# sch.net
KiCad netlist of a schematic drawn in Altium Designer
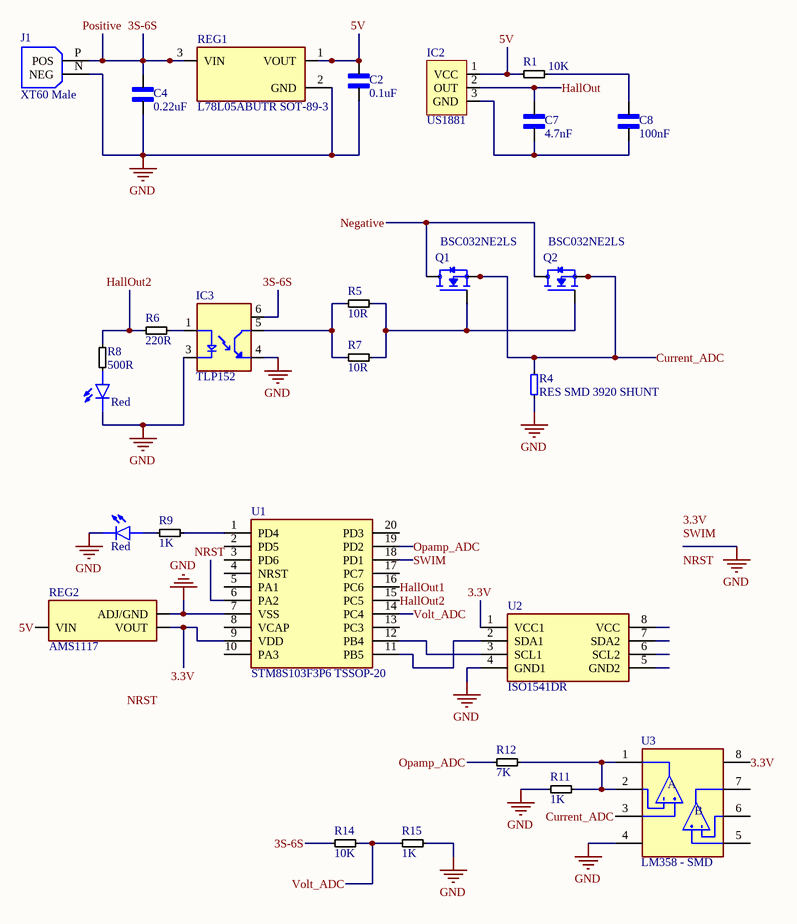
[diagram p0: sch.SchDoc]

(export (version "E")
  (design (tool "Eeschema 10.0.6"))
  (components
    (comp (ref "C2")
      (value "0.1uF")
      (footprint "0805 SMD CAP")
      (libsource (lib "MYS-Library") (part "CAP SMD 0805"))
    )
    (comp (ref "C4")
      (value "0.22uF")
      (footprint "0805 SMD CAP")
      (libsource (lib "MYS-Library") (part "CAP SMD 0805"))
    )
    (comp (ref "C7")
      (value "4.7nF")
      (footprint "0805 SMD CAP")
      (libsource (lib "MYS-Library") (part "CAP SMD 0805"))
    )
    (comp (ref "C8")
      (value "100nF")
      (footprint "0805 SMD CAP")
      (libsource (lib "MYS-Library") (part "CAP SMD 0805"))
    )
    (comp (ref "D2")
      (value "Red")
      (footprint "0805 SMD LED")
      (libsource (lib "MYS-Library") (part "LED 0805 SMD"))
    )
    (comp (ref "D3")
      (value "Red")
      (footprint "0805 SMD LED")
      (libsource (lib "MYS-Library") (part "LED 0805 SMD"))
    )
    (comp (ref "IC2") (value "US1881") (footprint "UA") (libsource (lib "MYS-Library") (part "US1881")))
    (comp (ref "IC3")
      (value "TLP152")
      (footprint "SOIC-6")
      (libsource (lib "MYS-Library") (part "TLP152-SMD"))
    )
    (comp (ref "J1")
      (value "XT60 Male")
      (footprint "XT60 Male Pin")
      (libsource (lib "MYS-Library") (part "XT60 Male Pin"))
    )
    (comp (ref "Q1")
      (value "BSC032NE2LS")
      (footprint "TDSON-8")
      (libsource (lib "MYS-Library") (part "TDSON-8 MOSFET"))
    )
    (comp (ref "Q2")
      (value "BSC032NE2LS")
      (footprint "TDSON-8")
      (libsource (lib "MYS-Library") (part "TDSON-8 MOSFET"))
    )
    (comp (ref "R1")
      (value "10K")
      (footprint "0805 SMD RES")
      (libsource (lib "MYS-Library") (part "RES SMD 0805"))
    )
    (comp (ref "R4")
      (value "RES SMD 3920 SHUNT")
      (footprint "RES 3920 SMD")
      (libsource (lib "MYS-Library") (part "RES SMD 3920 SHUNT"))
    )
    (comp (ref "R5")
      (value "10R")
      (footprint "0805 SMD RES")
      (libsource (lib "MYS-Library") (part "RES SMD 0805"))
    )
    (comp (ref "R6")
      (value "220R")
      (footprint "0805 SMD RES")
      (libsource (lib "MYS-Library") (part "RES SMD 0805"))
    )
    (comp (ref "R7")
      (value "10R")
      (footprint "0805 SMD RES")
      (libsource (lib "MYS-Library") (part "RES SMD 0805"))
    )
    (comp (ref "R8")
      (value "500R")
      (footprint "0805 SMD RES")
      (libsource (lib "MYS-Library") (part "RES SMD 0805"))
    )
    (comp (ref "R9")
      (value "1K")
      (footprint "0805 SMD RES")
      (libsource (lib "MYS-Library") (part "RES SMD 0805"))
    )
    (comp (ref "R11")
      (value "1K")
      (footprint "0805 SMD RES")
      (libsource (lib "MYS-Library") (part "RES SMD 0805"))
    )
    (comp (ref "R12")
      (value "7K")
      (footprint "0805 SMD RES")
      (libsource (lib "MYS-Library") (part "RES SMD 0805"))
    )
    (comp (ref "R14")
      (value "10K")
      (footprint "0805 SMD RES")
      (libsource (lib "MYS-Library") (part "RES SMD 0805"))
    )
    (comp (ref "R15")
      (value "1K")
      (footprint "0805 SMD RES")
      (libsource (lib "MYS-Library") (part "RES SMD 0805"))
    )
    (comp (ref "REG1")
      (value "L78L05ABUTR SOT-89-3")
      (footprint "SOT89-3")
      (libsource (lib "MYS-Library") (part "L78L05ABUTR"))
    )
    (comp (ref "REG2")
      (value "AMS1117")
      (footprint "SOT-223")
      (libsource (lib "MYS-Library") (part "AMS1117"))
    )
    (comp (ref "U1")
      (value "STM8S103F3P6 TSSOP-20")
      (footprint "TSSOP-20")
      (libsource (lib "MYS-Library") (part "STM8S103F3P6"))
    )
    (comp (ref "U2")
      (value "ISO1541DR")
      (footprint "SOIC-8")
      (libsource (lib "MYS-Library") (part "ISO1541DR"))
    )
    (comp (ref "U3")
      (value "LM358 - SMD")
      (footprint "SOIC-8")
      (libsource (lib "MYS-Library") (part "LM358 - SMD"))
    )
  )
  (nets
    (net (code "1") (name "/3.3V") (class "Default")
      (node (ref "REG2") (pin "2") (pinfunction "VOUT_2") (pintype "passive"))
      (node (ref "U1") (pin "9") (pinfunction "VDD_9") (pintype "passive"))
      (node (ref "U2") (pin "1") (pinfunction "VCC1_1") (pintype "passive"))
      (node (ref "U3") (pin "8") (pinfunction "V+_8") (pintype "passive"))
    )
    (net (code "2") (name "/3S-6S") (class "Default")
      (node (ref "C4") (pin "1") (pinfunction "1_1") (pintype "passive"))
      (node (ref "IC3") (pin "6") (pinfunction "Vcc_6") (pintype "passive"))
      (node (ref "J1") (pin "P") (pinfunction "POS_P") (pintype "passive"))
      (node (ref "R14") (pin "1") (pinfunction "1_1") (pintype "passive"))
      (node (ref "REG1") (pin "3") (pinfunction "VIN_3") (pintype "passive"))
    )
    (net (code "3") (name "/5V") (class "Default")
      (node (ref "C2") (pin "1") (pinfunction "1_1") (pintype "passive"))
      (node (ref "IC2") (pin "1") (pinfunction "VCC_1") (pintype "passive"))
      (node (ref "R1") (pin "1") (pinfunction "1_1") (pintype "passive"))
      (node (ref "REG1") (pin "1") (pinfunction "VOUT_1") (pintype "passive"))
      (node (ref "REG2") (pin "3") (pinfunction "VIN_3") (pintype "passive"))
    )
    (net (code "4") (name "/Current_ADC") (class "Default")
      (node (ref "Q1") (pin "1") (pinfunction "S_1") (pintype "passive"))
      (node (ref "Q1") (pin "2") (pinfunction "S_2") (pintype "passive"))
      (node (ref "Q1") (pin "3") (pinfunction "S_3") (pintype "passive"))
      (node (ref "Q2") (pin "1") (pinfunction "S_1") (pintype "passive"))
      (node (ref "Q2") (pin "2") (pinfunction "S_2") (pintype "passive"))
      (node (ref "Q2") (pin "3") (pinfunction "S_3") (pintype "passive"))
      (node (ref "R4") (pin "2") (pinfunction "2_2") (pintype "passive"))
      (node (ref "U3") (pin "3") (pinfunction "IN1+_3") (pintype "passive"))
    )
    (net (code "5") (name "/HallOut") (class "Default")
      (node (ref "C7") (pin "1") (pinfunction "1_1") (pintype "passive"))
      (node (ref "IC2") (pin "2") (pinfunction "OUT_2") (pintype "passive"))
    )
    (net (code "6") (name "/HallOut1") (class "Default")
      (node (ref "U1") (pin "16") (pinfunction "PC6_16") (pintype "passive"))
    )
    (net (code "7") (name "/HallOut2") (class "Default")
      (node (ref "R6") (pin "1") (pinfunction "1_1") (pintype "passive"))
      (node (ref "R8") (pin "2") (pinfunction "2_2") (pintype "passive"))
      (node (ref "U1") (pin "15") (pinfunction "PC5_15") (pintype "passive"))
    )
    (net (code "8") (name "/NRST") (class "Default")
      (node (ref "U1") (pin "6") (pinfunction "PA2_6") (pintype "passive"))
    )
    (net (code "9") (name "/Negative") (class "Default")
      (node (ref "Q1") (pin "5") (pinfunction "D_5") (pintype "passive"))
      (node (ref "Q2") (pin "5") (pinfunction "D_5") (pintype "passive"))
    )
    (net (code "10") (name "/Opamp_ADC") (class "Default")
      (node (ref "R12") (pin "1") (pinfunction "1_1") (pintype "passive"))
      (node (ref "U1") (pin "19") (pinfunction "PD2_19") (pintype "passive"))
    )
    (net (code "11") (name "/SWIM") (class "Default")
      (node (ref "U1") (pin "18") (pinfunction "PD1_18") (pintype "passive"))
    )
    (net (code "12") (name "/Volt_ADC") (class "Default")
      (node (ref "R14") (pin "2") (pinfunction "2_2") (pintype "passive"))
      (node (ref "R15") (pin "1") (pinfunction "1_1") (pintype "passive"))
      (node (ref "U1") (pin "14") (pinfunction "PC4_14") (pintype "passive"))
    )
    (net (code "13") (name "GND") (class "Default")
      (node (ref "C2") (pin "2") (pinfunction "2_2") (pintype "passive"))
      (node (ref "C4") (pin "2") (pinfunction "2_2") (pintype "passive"))
      (node (ref "D2") (pin "C") (pinfunction "C_C") (pintype "passive"))
      (node (ref "D3") (pin "C") (pinfunction "C_C") (pintype "passive"))
      (node (ref "IC3") (pin "3") (pinfunction "C_3") (pintype "passive"))
      (node (ref "IC3") (pin "4") (pinfunction "GND_4") (pintype "passive"))
      (node (ref "J1") (pin "N") (pinfunction "NEG_N") (pintype "passive"))
      (node (ref "R11") (pin "1") (pinfunction "1_1") (pintype "passive"))
      (node (ref "R15") (pin "2") (pinfunction "2_2") (pintype "passive"))
      (node (ref "R4") (pin "1") (pinfunction "1_1") (pintype "passive"))
      (node (ref "REG1") (pin "2") (pinfunction "GND_2") (pintype "passive"))
      (node (ref "REG2") (pin "1") (pinfunction "ADJ/GND_1") (pintype "power_in"))
      (node (ref "U1") (pin "7") (pinfunction "VSS_7") (pintype "passive"))
      (node (ref "U2") (pin "4") (pinfunction "GND1_4") (pintype "passive"))
      (node (ref "U3") (pin "4") (pinfunction "V-_4") (pintype "passive"))
    )
    (net (code "14") (name "Net-(C8-Pad1)") (class "Default")
      (node (ref "C8") (pin "1") (pinfunction "1_1") (pintype "passive"))
      (node (ref "R1") (pin "2") (pinfunction "2_2") (pintype "passive"))
    )
    (net (code "15") (name "Net-(D2-PadA)") (class "Default")
      (node (ref "D2") (pin "A") (pinfunction "A_A") (pintype "passive"))
      (node (ref "R8") (pin "1") (pinfunction "1_1") (pintype "passive"))
    )
    (net (code "16") (name "Net-(D3-PadA)") (class "Default")
      (node (ref "D3") (pin "A") (pinfunction "A_A") (pintype "passive"))
      (node (ref "R9") (pin "2") (pinfunction "2_2") (pintype "passive"))
    )
    (net (code "17") (name "Net-(IC2-GND)") (class "Default")
      (node (ref "C7") (pin "2") (pinfunction "2_2") (pintype "passive"))
      (node (ref "C8") (pin "2") (pinfunction "2_2") (pintype "passive"))
      (node (ref "IC2") (pin "3") (pinfunction "GND_3") (pintype "passive"))
    )
    (net (code "18") (name "Net-(IC3-A)") (class "Default")
      (node (ref "IC3") (pin "1") (pinfunction "A_1") (pintype "passive"))
      (node (ref "R6") (pin "2") (pinfunction "2_2") (pintype "passive"))
    )
    (net (code "19") (name "Net-(IC3-Vo)") (class "Default")
      (node (ref "IC3") (pin "5") (pinfunction "Vo_5") (pintype "passive"))
      (node (ref "R5") (pin "1") (pinfunction "1_1") (pintype "passive"))
      (node (ref "R7") (pin "1") (pinfunction "1_1") (pintype "passive"))
    )
    (net (code "20") (name "Net-(Q1-G)") (class "Default")
      (node (ref "Q1") (pin "4") (pinfunction "G_4") (pintype "passive"))
      (node (ref "Q2") (pin "4") (pinfunction "G_4") (pintype "passive"))
      (node (ref "R5") (pin "2") (pinfunction "2_2") (pintype "passive"))
      (node (ref "R7") (pin "2") (pinfunction "2_2") (pintype "passive"))
    )
    (net (code "21") (name "Net-(U1-PB4)") (class "Default")
      (node (ref "U1") (pin "12") (pinfunction "PB4_12") (pintype "passive"))
      (node (ref "U2") (pin "3") (pinfunction "SCL1_3") (pintype "passive"))
    )
    (net (code "22") (name "Net-(U1-PB5)") (class "Default")
      (node (ref "U1") (pin "11") (pinfunction "PB5_11") (pintype "passive"))
      (node (ref "U2") (pin "2") (pinfunction "SDA1_2") (pintype "passive"))
    )
    (net (code "23") (name "Net-(U1-PD4)") (class "Default")
      (node (ref "R9") (pin "1") (pinfunction "1_1") (pintype "passive"))
      (node (ref "U1") (pin "1") (pinfunction "PD4_1") (pintype "passive"))
    )
    (net (code "24") (name "Net-(U3-IN1-)") (class "Default")
      (node (ref "R11") (pin "2") (pinfunction "2_2") (pintype "passive"))
      (node (ref "R12") (pin "2") (pinfunction "2_2") (pintype "passive"))
      (node (ref "U3") (pin "1") (pinfunction "OUT1_1") (pintype "passive"))
      (node (ref "U3") (pin "2") (pinfunction "IN1-_2") (pintype "passive"))
    )
    (net (code "25") (name "unconnected-(U1-NRST-Pad4)") (class "Default")
      (node (ref "U1") (pin "4") (pinfunction "NRST_4") (pintype "passive"))
    )
    (net (code "26") (name "unconnected-(U1-PA1-Pad5)") (class "Default")
      (node (ref "U1") (pin "5") (pinfunction "PA1_5") (pintype "passive"))
    )
    (net (code "27") (name "unconnected-(U1-PA3-Pad10)") (class "Default")
      (node (ref "U1") (pin "10") (pinfunction "PA3_10") (pintype "passive"))
    )
    (net (code "28") (name "unconnected-(U1-PC3-Pad13)") (class "Default")
      (node (ref "U1") (pin "13") (pinfunction "PC3_13") (pintype "passive"))
    )
    (net (code "29") (name "unconnected-(U1-PC7-Pad17)") (class "Default")
      (node (ref "U1") (pin "17") (pinfunction "PC7_17") (pintype "passive"))
    )
    (net (code "30") (name "unconnected-(U1-PD3-Pad20)") (class "Default")
      (node (ref "U1") (pin "20") (pinfunction "PD3_20") (pintype "passive"))
    )
    (net (code "31") (name "unconnected-(U1-PD5-Pad2)") (class "Default")
      (node (ref "U1") (pin "2") (pinfunction "PD5_2") (pintype "passive"))
    )
    (net (code "32") (name "unconnected-(U1-PD6-Pad3)") (class "Default")
      (node (ref "U1") (pin "3") (pinfunction "PD6_3") (pintype "passive"))
    )
    (net (code "33") (name "unconnected-(U1-VCAP-Pad8)") (class "Default")
      (node (ref "U1") (pin "8") (pinfunction "VCAP_8") (pintype "passive"))
    )
    (net (code "34") (name "unconnected-(U2-GND2-Pad5)") (class "Default")
      (node (ref "U2") (pin "5") (pinfunction "GND2_5") (pintype "passive"))
    )
    (net (code "35") (name "unconnected-(U2-SCL2-Pad6)") (class "Default")
      (node (ref "U2") (pin "6") (pinfunction "SCL2_6") (pintype "passive"))
    )
    (net (code "36") (name "unconnected-(U2-SDA2-Pad7)") (class "Default")
      (node (ref "U2") (pin "7") (pinfunction "SDA2_7") (pintype "passive"))
    )
    (net (code "37") (name "unconnected-(U2-VCC-Pad8)") (class "Default")
      (node (ref "U2") (pin "8") (pinfunction "VCC_8") (pintype "passive"))
    )
    (net (code "38") (name "unconnected-(U3-IN2+-Pad5)") (class "Default")
      (node (ref "U3") (pin "5") (pinfunction "IN2+_5") (pintype "passive"))
    )
    (net (code "39") (name "unconnected-(U3-IN2--Pad6)") (class "Default")
      (node (ref "U3") (pin "6") (pinfunction "IN2-_6") (pintype "passive"))
    )
    (net (code "40") (name "unconnected-(U3-OUT2-Pad7)") (class "Default")
      (node (ref "U3") (pin "7") (pinfunction "OUT2_7") (pintype "passive"))
    )
  )
)
